# mcu.net
KiCad netlist of a schematic drawn in Altium Designer
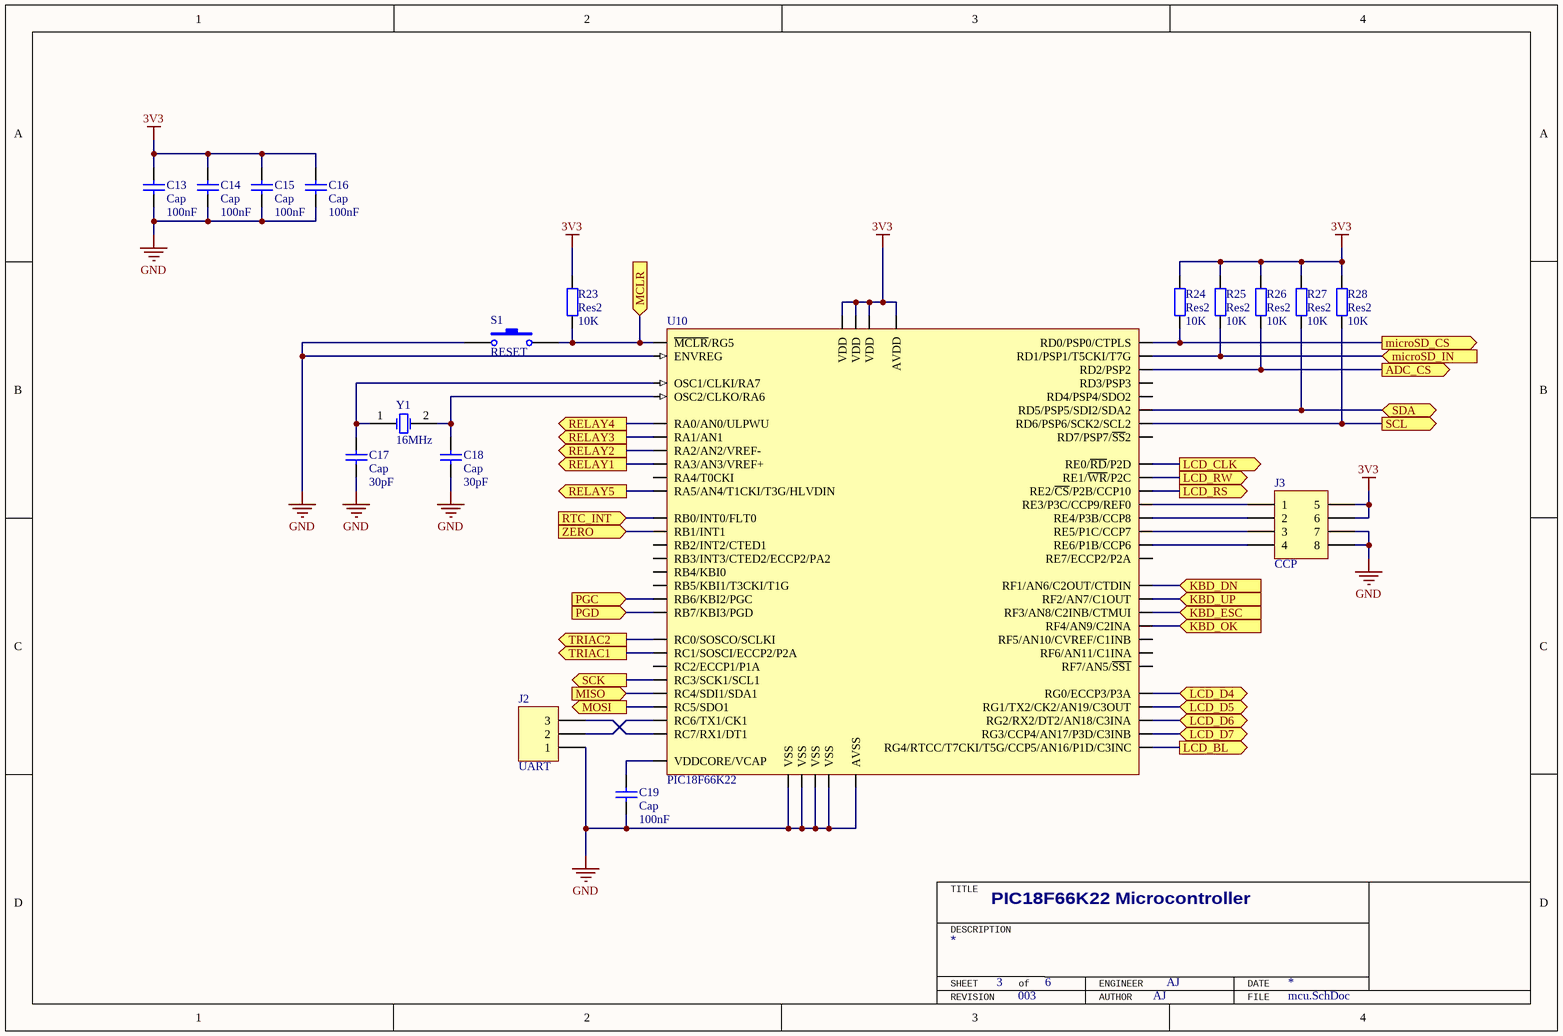
[diagram p0: mcu.SchDoc]

(export (version "E")
  (design (tool "Eeschema 10.0.6"))
  (components
    (comp (ref "C13")
      (value "Cap")
      (footprint "0603")
      (description "Capacitor")
      (fields (field (name "ALTIUM_VALUE") "100nF") (field (name "PUBLISHER") "Altium Limited"))
      (libsource (lib "Miscellaneous Devices") (part "Cap"))
    )
    (comp (ref "C14")
      (value "Cap")
      (footprint "0603")
      (description "Capacitor")
      (fields (field (name "ALTIUM_VALUE") "100nF") (field (name "PUBLISHER") "Altium Limited"))
      (libsource (lib "Miscellaneous Devices") (part "Cap"))
    )
    (comp (ref "C15")
      (value "Cap")
      (footprint "0603")
      (description "Capacitor")
      (fields (field (name "ALTIUM_VALUE") "100nF") (field (name "PUBLISHER") "Altium Limited"))
      (libsource (lib "Miscellaneous Devices") (part "Cap"))
    )
    (comp (ref "C16")
      (value "Cap")
      (footprint "0603")
      (description "Capacitor")
      (fields (field (name "ALTIUM_VALUE") "100nF") (field (name "PUBLISHER") "Altium Limited"))
      (libsource (lib "Miscellaneous Devices") (part "Cap"))
    )
    (comp (ref "C17")
      (value "Cap")
      (footprint "0603")
      (description "Capacitor")
      (fields (field (name "ALTIUM_VALUE") "30pF") (field (name "PUBLISHER") "Altium Limited"))
      (libsource (lib "Miscellaneous Devices") (part "Cap"))
    )
    (comp (ref "C18")
      (value "Cap")
      (footprint "0603")
      (description "Capacitor")
      (fields (field (name "ALTIUM_VALUE") "30pF") (field (name "PUBLISHER") "Altium Limited"))
      (libsource (lib "Miscellaneous Devices") (part "Cap"))
    )
    (comp (ref "C19")
      (value "Cap")
      (footprint "0603")
      (description "Capacitor")
      (fields (field (name "ALTIUM_VALUE") "100nF") (field (name "PUBLISHER") "Altium Limited"))
      (libsource (lib "Miscellaneous Devices") (part "Cap"))
    )
    (comp (ref "J2")
      (value "UART")
      (footprint "HDR1X3")
      (description "Header, 3-Pin")
      (fields (field (name "PUBLISHER") "Altium Limited"))
      (libsource (lib "Miscellaneous Connectors") (part "Header 3"))
    )
    (comp (ref "J3")
      (value "CCP")
      (footprint "HDR2X4_CEN")
      (description "Header, 4-Pin, Dual row")
      (fields (field (name "PUBLISHER") "Altium Limited"))
      (libsource (lib "Miscellaneous Connectors") (part "Header 4X2A"))
    )
    (comp (ref "R23")
      (value "Res2")
      (footprint "0603")
      (description "Resistor")
      (fields (field (name "ALTIUM_VALUE") "10K") (field (name "PUBLISHER") "Altium Limited"))
      (libsource (lib "Miscellaneous Devices") (part "Res2"))
    )
    (comp (ref "R24")
      (value "Res2")
      (footprint "0603")
      (description "Resistor")
      (fields (field (name "ALTIUM_VALUE") "10K") (field (name "PUBLISHER") "Altium Limited"))
      (libsource (lib "") (part "Res2_1"))
    )
    (comp (ref "R25")
      (value "Res2")
      (footprint "0603")
      (description "Resistor")
      (fields (field (name "ALTIUM_VALUE") "10K") (field (name "PUBLISHER") "Altium Limited"))
      (libsource (lib "") (part "Res2_1"))
    )
    (comp (ref "R26")
      (value "Res2")
      (footprint "0603")
      (description "Resistor")
      (fields (field (name "ALTIUM_VALUE") "10K") (field (name "PUBLISHER") "Altium Limited"))
      (libsource (lib "") (part "Res2_1"))
    )
    (comp (ref "R27")
      (value "Res2")
      (footprint "0603")
      (description "Resistor")
      (fields (field (name "ALTIUM_VALUE") "10K") (field (name "PUBLISHER") "Altium Limited"))
      (libsource (lib "Miscellaneous Devices") (part "Res2"))
    )
    (comp (ref "R28")
      (value "Res2")
      (footprint "0603")
      (description "Resistor")
      (fields (field (name "ALTIUM_VALUE") "10K") (field (name "PUBLISHER") "Altium Limited"))
      (libsource (lib "Miscellaneous Devices") (part "Res2"))
    )
    (comp (ref "S1")
      (value "RESET")
      (footprint "Switch 2")
      (description "Switch")
      (fields (field (name "PUBLISHER") "Altium Limited"))
      (libsource (lib "Miscellaneous Devices") (part "SW-PB"))
    )
    (comp (ref "U10")
      (value "PIC18F66K22")
      (footprint "TQFP-64")
      (description "PIC microcontroller")
      (libsource (lib "AJ") (part "PIC18F66K22"))
    )
    (comp (ref "Y1")
      (value "16MHz")
      (footprint "XTAL")
      (description "Crystal Oscillator")
      (fields (field (name "PUBLISHER") "Altium Limited"))
      (libsource (lib "Miscellaneous Devices") (part "XTAL"))
    )
  )
  (nets
    (net (code "1") (name "/ADC_CS") (class "Default")
      (node (ref "R26") (pin "1") (pinfunction "1_1") (pintype "passive"))
      (node (ref "U10") (pin "54") (pinfunction "RD2/PSP2_54") (pintype "bidirectional"))
    )
    (net (code "2") (name "/KBD_DN") (class "Default")
      (node (ref "U10") (pin "17") (pinfunction "RF1/AN6/C2OUT/CTDIN_17") (pintype "bidirectional"))
    )
    (net (code "3") (name "/KBD_ESC") (class "Default")
      (node (ref "U10") (pin "15") (pinfunction "RF3/AN8/C2INB/CTMUI_15") (pintype "bidirectional"))
    )
    (net (code "4") (name "/KBD_OK") (class "Default")
      (node (ref "U10") (pin "14") (pinfunction "RF4/AN9/C2INA_14") (pintype "bidirectional"))
    )
    (net (code "5") (name "/KBD_UP") (class "Default")
      (node (ref "U10") (pin "16") (pinfunction "RF2/AN7/C1OUT_16") (pintype "bidirectional"))
    )
    (net (code "6") (name "/LCD_BL") (class "Default")
      (node (ref "U10") (pin "8") (pinfunction "RG4/RTCC/T7CKI/T5G/CCP5/AN16/P1D/C3INC_8") (pintype "bidirectional"))
    )
    (net (code "7") (name "/LCD_CLK") (class "Default")
      (node (ref "U10") (pin "2") (pinfunction "RE0/~{RD}/P2D_2") (pintype "bidirectional"))
    )
    (net (code "8") (name "/LCD_D4") (class "Default")
      (node (ref "U10") (pin "3") (pinfunction "RG0/ECCP3/P3A_3") (pintype "bidirectional"))
    )
    (net (code "9") (name "/LCD_D5") (class "Default")
      (node (ref "U10") (pin "4") (pinfunction "RG1/TX2/CK2/AN19/C3OUT_4") (pintype "bidirectional"))
    )
    (net (code "10") (name "/LCD_D6") (class "Default")
      (node (ref "U10") (pin "5") (pinfunction "RG2/RX2/DT2/AN18/C3INA_5") (pintype "bidirectional"))
    )
    (net (code "11") (name "/LCD_D7") (class "Default")
      (node (ref "U10") (pin "6") (pinfunction "RG3/CCP4/AN17/P3D/C3INB_6") (pintype "bidirectional"))
    )
    (net (code "12") (name "/LCD_RS") (class "Default")
      (node (ref "U10") (pin "64") (pinfunction "RE2/~{CS}/P2B/CCP10_64") (pintype "bidirectional"))
    )
    (net (code "13") (name "/LCD_RW") (class "Default")
      (node (ref "U10") (pin "1") (pinfunction "RE1/~{WR}/P2C_1") (pintype "bidirectional"))
    )
    (net (code "14") (name "/MCLR") (class "Default")
      (node (ref "R23") (pin "1") (pinfunction "1_1") (pintype "passive"))
      (node (ref "S1") (pin "2") (pinfunction "2_2") (pintype "passive"))
      (node (ref "U10") (pin "7") (pinfunction "~{MCLR}/RG5_7") (pintype "bidirectional"))
    )
    (net (code "15") (name "/MISO") (class "Default")
      (node (ref "U10") (pin "35") (pinfunction "RC4/SDI1/SDA1_35") (pintype "bidirectional"))
    )
    (net (code "16") (name "/MOSI") (class "Default")
      (node (ref "U10") (pin "36") (pinfunction "RC5/SDO1_36") (pintype "bidirectional"))
    )
    (net (code "17") (name "/PGC") (class "Default")
      (node (ref "U10") (pin "42") (pinfunction "RB6/KBI2/PGC_42") (pintype "bidirectional"))
    )
    (net (code "18") (name "/PGD") (class "Default")
      (node (ref "U10") (pin "37") (pinfunction "RB7/KBI3/PGD_37") (pintype "bidirectional"))
    )
    (net (code "19") (name "/RELAY1") (class "Default")
      (node (ref "U10") (pin "21") (pinfunction "RA3/AN3/VREF+_21") (pintype "bidirectional"))
    )
    (net (code "20") (name "/RELAY2") (class "Default")
      (node (ref "U10") (pin "22") (pinfunction "RA2/AN2/VREF-_22") (pintype "bidirectional"))
    )
    (net (code "21") (name "/RELAY3") (class "Default")
      (node (ref "U10") (pin "23") (pinfunction "RA1/AN1_23") (pintype "bidirectional"))
    )
    (net (code "22") (name "/RELAY4") (class "Default")
      (node (ref "U10") (pin "24") (pinfunction "RA0/AN0/ULPWU_24") (pintype "bidirectional"))
    )
    (net (code "23") (name "/RELAY5") (class "Default")
      (node (ref "U10") (pin "27") (pinfunction "RA5/AN4/T1CKI/T3G/HLVDIN_27") (pintype "bidirectional"))
    )
    (net (code "24") (name "/RTC_INT") (class "Default")
      (node (ref "U10") (pin "48") (pinfunction "RB0/INT0/FLT0_48") (pintype "bidirectional"))
    )
    (net (code "25") (name "/SCK") (class "Default")
      (node (ref "U10") (pin "34") (pinfunction "RC3/SCK1/SCL1_34") (pintype "bidirectional"))
    )
    (net (code "26") (name "/SCL") (class "Default")
      (node (ref "R28") (pin "1") (pinfunction "1_1") (pintype "passive"))
      (node (ref "U10") (pin "50") (pinfunction "RD6/PSP6/SCK2/SCL2_50") (pintype "bidirectional"))
    )
    (net (code "27") (name "/SDA") (class "Default")
      (node (ref "R27") (pin "1") (pinfunction "1_1") (pintype "passive"))
      (node (ref "U10") (pin "51") (pinfunction "RD5/PSP5/SDI2/SDA2_51") (pintype "bidirectional"))
    )
    (net (code "28") (name "/TRIAC1") (class "Default")
      (node (ref "U10") (pin "29") (pinfunction "RC1/SOSCI/ECCP2/P2A_29") (pintype "bidirectional"))
    )
    (net (code "29") (name "/TRIAC2") (class "Default")
      (node (ref "U10") (pin "30") (pinfunction "RC0/SOSCO/SCLKI_30") (pintype "bidirectional"))
    )
    (net (code "30") (name "/ZERO") (class "Default")
      (node (ref "U10") (pin "47") (pinfunction "RB1/INT1_47") (pintype "bidirectional"))
    )
    (net (code "31") (name "/microSD_CS") (class "Default")
      (node (ref "R24") (pin "1") (pinfunction "1_1") (pintype "passive"))
      (node (ref "U10") (pin "58") (pinfunction "RD0/PSP0/CTPLS_58") (pintype "bidirectional"))
    )
    (net (code "32") (name "/microSD_IN") (class "Default")
      (node (ref "R25") (pin "1") (pinfunction "1_1") (pintype "passive"))
      (node (ref "U10") (pin "55") (pinfunction "RD1/PSP1/T5CKI/T7G_55") (pintype "bidirectional"))
    )
    (net (code "33") (name "3V3") (class "Default")
      (node (ref "C13") (pin "2") (pinfunction "2_2") (pintype "passive"))
      (node (ref "C14") (pin "2") (pinfunction "2_2") (pintype "passive"))
      (node (ref "C15") (pin "2") (pinfunction "2_2") (pintype "passive"))
      (node (ref "C16") (pin "2") (pinfunction "2_2") (pintype "passive"))
      (node (ref "J3") (pin "5") (pinfunction "5_5") (pintype "passive"))
      (node (ref "J3") (pin "6") (pinfunction "6_6") (pintype "passive"))
      (node (ref "R23") (pin "2") (pinfunction "2_2") (pintype "passive"))
      (node (ref "R24") (pin "2") (pinfunction "2_2") (pintype "passive"))
      (node (ref "R25") (pin "2") (pinfunction "2_2") (pintype "passive"))
      (node (ref "R26") (pin "2") (pinfunction "2_2") (pintype "passive"))
      (node (ref "R27") (pin "2") (pinfunction "2_2") (pintype "passive"))
      (node (ref "R28") (pin "2") (pinfunction "2_2") (pintype "passive"))
      (node (ref "U10") (pin "19") (pinfunction "AVDD_19") (pintype "power_in"))
      (node (ref "U10") (pin "26") (pinfunction "VDD_26") (pintype "power_in"))
      (node (ref "U10") (pin "38") (pinfunction "VDD_38") (pintype "power_in"))
      (node (ref "U10") (pin "57") (pinfunction "VDD_57") (pintype "power_in"))
    )
    (net (code "34") (name "GND") (class "Default")
      (node (ref "C13") (pin "1") (pinfunction "1_1") (pintype "passive"))
      (node (ref "C14") (pin "1") (pinfunction "1_1") (pintype "passive"))
      (node (ref "C15") (pin "1") (pinfunction "1_1") (pintype "passive"))
      (node (ref "C16") (pin "1") (pinfunction "1_1") (pintype "passive"))
      (node (ref "C17") (pin "1") (pinfunction "1_1") (pintype "passive"))
      (node (ref "C18") (pin "1") (pinfunction "1_1") (pintype "passive"))
      (node (ref "C19") (pin "1") (pinfunction "1_1") (pintype "passive"))
      (node (ref "J2") (pin "1") (pinfunction "1_1") (pintype "passive"))
      (node (ref "J3") (pin "7") (pinfunction "7_7") (pintype "passive"))
      (node (ref "J3") (pin "8") (pinfunction "8_8") (pintype "passive"))
      (node (ref "S1") (pin "1") (pinfunction "1_1") (pintype "passive"))
      (node (ref "U10") (pin "18") (pinfunction "ENVREG_18") (pintype "input"))
      (node (ref "U10") (pin "20") (pinfunction "AVSS_20") (pintype "power_in"))
      (node (ref "U10") (pin "25") (pinfunction "VSS_25") (pintype "power_in"))
      (node (ref "U10") (pin "41") (pinfunction "VSS_41") (pintype "power_in"))
      (node (ref "U10") (pin "56") (pinfunction "VSS_56") (pintype "power_in"))
      (node (ref "U10") (pin "9") (pinfunction "VSS_9") (pintype "power_in"))
    )
    (net (code "35") (name "Net-(U10-OSC1{slash}CLKI{slash}RA7)") (class "Default")
      (node (ref "C17") (pin "2") (pinfunction "2_2") (pintype "passive"))
      (node (ref "U10") (pin "39") (pinfunction "OSC1/CLKI/RA7_39") (pintype "input"))
      (node (ref "Y1") (pin "1") (pinfunction "OSC1_1") (pintype "passive"))
    )
    (net (code "36") (name "Net-(U10-OSC2{slash}CLKO{slash}RA6)") (class "Default")
      (node (ref "C18") (pin "2") (pinfunction "2_2") (pintype "passive"))
      (node (ref "U10") (pin "40") (pinfunction "OSC2/CLKO/RA6_40") (pintype "input"))
      (node (ref "Y1") (pin "2") (pinfunction "OSC2_2") (pintype "passive"))
    )
    (net (code "37") (name "Net-(U10-RC6{slash}TX1{slash}CK1)") (class "Default")
      (node (ref "J2") (pin "2") (pinfunction "2_2") (pintype "passive"))
      (node (ref "U10") (pin "31") (pinfunction "RC6/TX1/CK1_31") (pintype "bidirectional"))
    )
    (net (code "38") (name "Net-(U10-RC7{slash}RX1{slash}DT1)") (class "Default")
      (node (ref "J2") (pin "3") (pinfunction "3_3") (pintype "passive"))
      (node (ref "U10") (pin "32") (pinfunction "RC7/RX1/DT1_32") (pintype "bidirectional"))
    )
    (net (code "39") (name "Net-(U10-RE3{slash}P3C{slash}CCP9{slash}REF0)") (class "Default")
      (node (ref "J3") (pin "1") (pinfunction "1_1") (pintype "passive"))
      (node (ref "U10") (pin "63") (pinfunction "RE3/P3C/CCP9/REF0_63") (pintype "bidirectional"))
    )
    (net (code "40") (name "Net-(U10-RE4{slash}P3B{slash}CCP8)") (class "Default")
      (node (ref "J3") (pin "2") (pinfunction "2_2") (pintype "passive"))
      (node (ref "U10") (pin "62") (pinfunction "RE4/P3B/CCP8_62") (pintype "bidirectional"))
    )
    (net (code "41") (name "Net-(U10-RE5{slash}P1C{slash}CCP7)") (class "Default")
      (node (ref "J3") (pin "3") (pinfunction "3_3") (pintype "passive"))
      (node (ref "U10") (pin "61") (pinfunction "RE5/P1C/CCP7_61") (pintype "bidirectional"))
    )
    (net (code "42") (name "Net-(U10-RE6{slash}P1B{slash}CCP6)") (class "Default")
      (node (ref "J3") (pin "4") (pinfunction "4_4") (pintype "passive"))
      (node (ref "U10") (pin "60") (pinfunction "RE6/P1B/CCP6_60") (pintype "bidirectional"))
    )
    (net (code "43") (name "Net-(U10-VDDCORE{slash}VCAP)") (class "Default")
      (node (ref "C19") (pin "2") (pinfunction "2_2") (pintype "passive"))
      (node (ref "U10") (pin "10") (pinfunction "VDDCORE/VCAP_10") (pintype "power_in"))
    )
    (net (code "44") (name "unconnected-(U10-RA4{slash}T0CKI-Pad28)") (class "Default")
      (node (ref "U10") (pin "28") (pinfunction "RA4/T0CKI_28") (pintype "bidirectional"))
    )
    (net (code "45") (name "unconnected-(U10-RB2{slash}INT2{slash}CTED1-Pad46)") (class "Default")
      (node (ref "U10") (pin "46") (pinfunction "RB2/INT2/CTED1_46") (pintype "bidirectional"))
    )
    (net (code "46") (name "unconnected-(U10-RB3{slash}INT3{slash}CTED2{slash}ECCP2{slash}PA2-Pad45)") (class "Default")
      (node (ref "U10") (pin "45") (pinfunction "RB3/INT3/CTED2/ECCP2/PA2_45") (pintype "bidirectional"))
    )
    (net (code "47") (name "unconnected-(U10-RB4{slash}KBI0-Pad44)") (class "Default")
      (node (ref "U10") (pin "44") (pinfunction "RB4/KBI0_44") (pintype "bidirectional"))
    )
    (net (code "48") (name "unconnected-(U10-RB5{slash}KBI1{slash}T3CKI{slash}T1G-Pad43)") (class "Default")
      (node (ref "U10") (pin "43") (pinfunction "RB5/KBI1/T3CKI/T1G_43") (pintype "bidirectional"))
    )
    (net (code "49") (name "unconnected-(U10-RC2{slash}ECCP1{slash}P1A-Pad33)") (class "Default")
      (node (ref "U10") (pin "33") (pinfunction "RC2/ECCP1/P1A_33") (pintype "bidirectional"))
    )
    (net (code "50") (name "unconnected-(U10-RD3{slash}PSP3-Pad53)") (class "Default")
      (node (ref "U10") (pin "53") (pinfunction "RD3/PSP3_53") (pintype "bidirectional"))
    )
    (net (code "51") (name "unconnected-(U10-RD4{slash}PSP4{slash}SDO2-Pad52)") (class "Default")
      (node (ref "U10") (pin "52") (pinfunction "RD4/PSP4/SDO2_52") (pintype "bidirectional"))
    )
    (net (code "52") (name "unconnected-(U10-RD7{slash}PSP7{slash}~{SS}2-Pad49)") (class "Default")
      (node (ref "U10") (pin "49") (pinfunction "RD7/PSP7/~{SS}2_49") (pintype "bidirectional"))
    )
    (net (code "53") (name "unconnected-(U10-RE7{slash}ECCP2{slash}P2A-Pad59)") (class "Default")
      (node (ref "U10") (pin "59") (pinfunction "RE7/ECCP2/P2A_59") (pintype "bidirectional"))
    )
    (net (code "54") (name "unconnected-(U10-RF5{slash}AN10{slash}CVREF{slash}C1INB-Pad13)") (class "Default")
      (node (ref "U10") (pin "13") (pinfunction "RF5/AN10/CVREF/C1INB_13") (pintype "bidirectional"))
    )
    (net (code "55") (name "unconnected-(U10-RF6{slash}AN11{slash}C1INA-Pad12)") (class "Default")
      (node (ref "U10") (pin "12") (pinfunction "RF6/AN11/C1INA_12") (pintype "bidirectional"))
    )
    (net (code "56") (name "unconnected-(U10-RF7{slash}AN5{slash}~{SS1}-Pad11)") (class "Default")
      (node (ref "U10") (pin "11") (pinfunction "RF7/AN5/~{SS1}_11") (pintype "bidirectional"))
    )
  )
)
